# 4_Drivers.net
KiCad netlist of a schematic drawn in Altium Designer
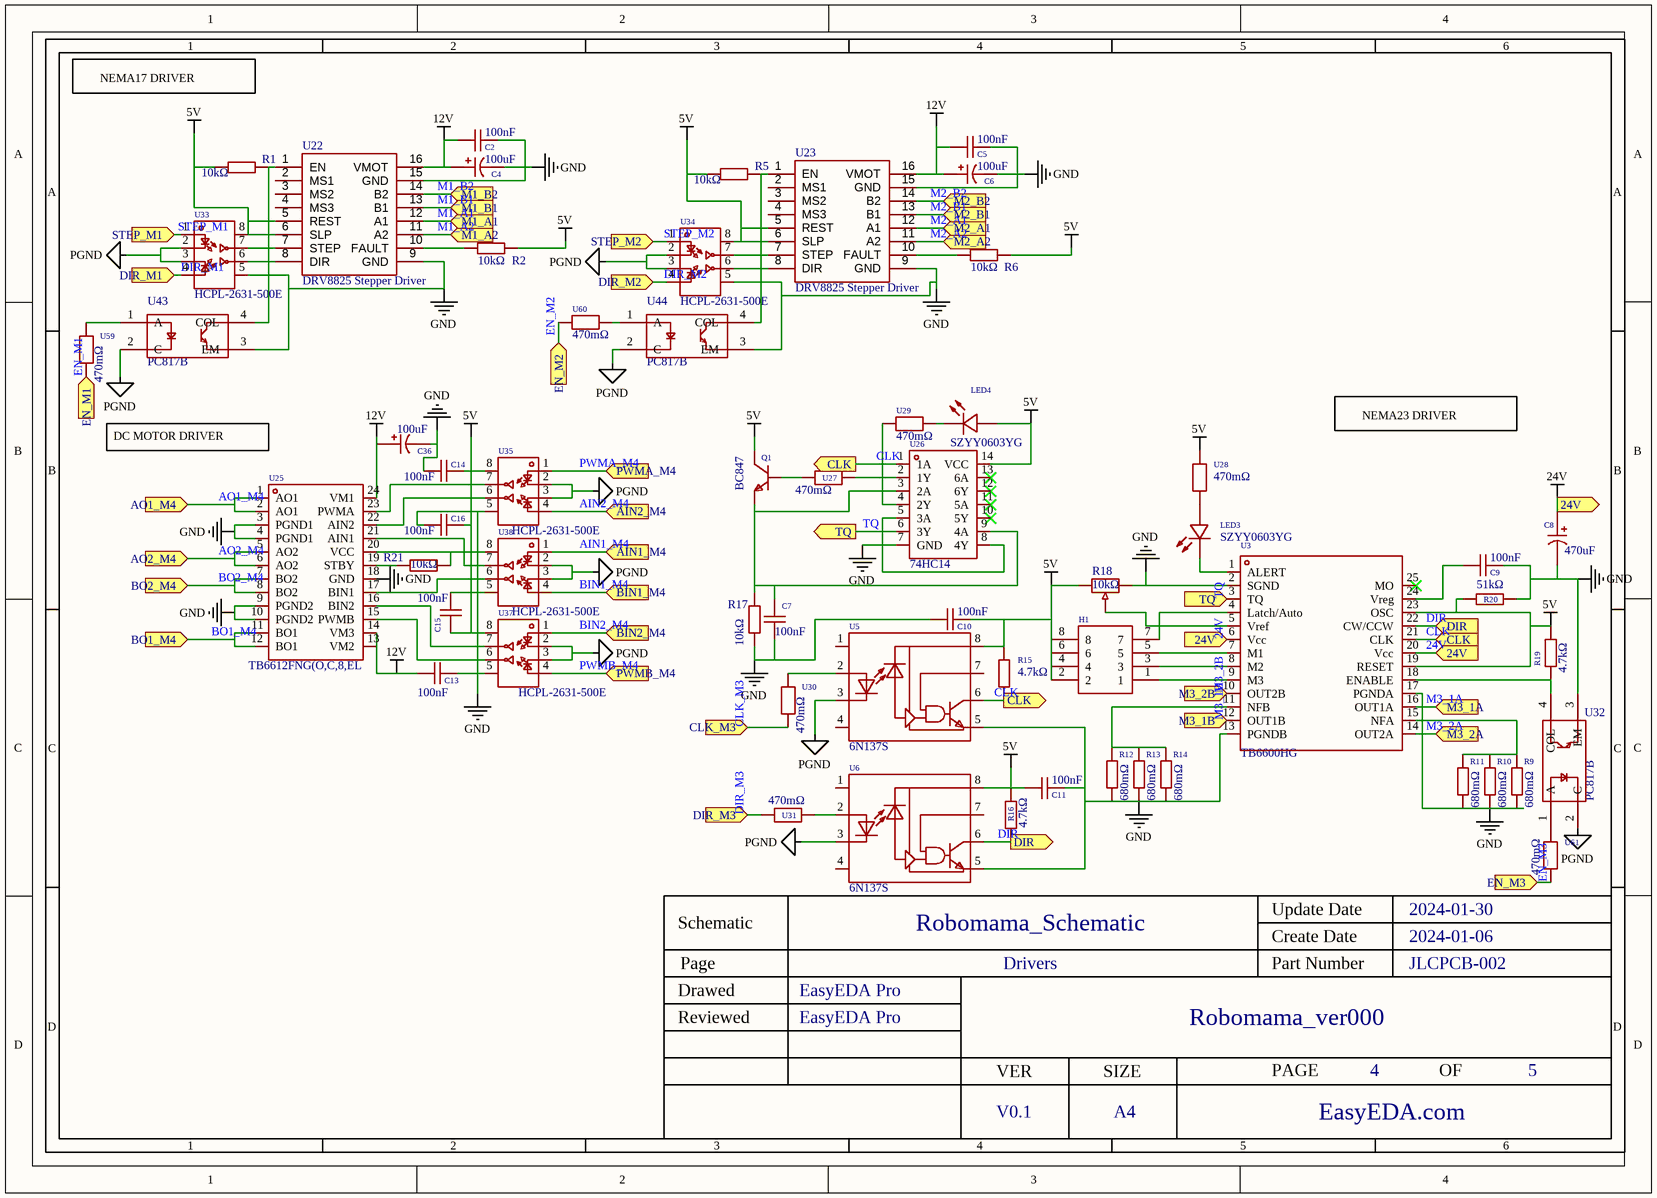
[diagram p0: 4_Drivers.schdoc]

(export (version "E")
  (design (tool "Eeschema 10.0.6"))
  (components
    (comp (ref "C2")
      (value "100nF")
      (footprint "C0603")
      (fields
        (field (name "MANUFACTURER") "FH(风华)")
        (field (name "MANUFACTURER PART") "0603B104K500NT")
        (field (name "TOLERANCE") "±10%")
      )
      (libsource (lib "altium-import") (part "root_0_0603B104K500NT_C30926_"))
    )
    (comp (ref "C4")
      (value "100uF")
      (footprint "CAP-SMD_BD6.3-L6.6-W6.6-LS7.2-FD")
      (fields
        (field (name "MANUFACTURER") "KNSCHA(科尼盛)")
        (field (name "MANUFACTURER PART") "RST100UF25V006")
        (field (name "TOLERANCE") "±20%")
      )
      (libsource (lib "altium-import") (part "root_0_RST100UF25V006_"))
    )
    (comp (ref "C5")
      (value "100nF")
      (footprint "C0603")
      (fields
        (field (name "MANUFACTURER") "FH(风华)")
        (field (name "MANUFACTURER PART") "0603B104K500NT")
        (field (name "TOLERANCE") "±10%")
      )
      (libsource (lib "altium-import") (part "root_0_0603B104K500NT_C30926_"))
    )
    (comp (ref "C6")
      (value "100uF")
      (footprint "CAP-SMD_BD6.3-L6.6-W6.6-LS7.2-FD")
      (fields
        (field (name "MANUFACTURER") "KNSCHA(科尼盛)")
        (field (name "MANUFACTURER PART") "RST100UF25V006")
        (field (name "TOLERANCE") "±20%")
      )
      (libsource (lib "altium-import") (part "root_0_RST100UF25V006_"))
    )
    (comp (ref "C7")
      (value "100nF")
      (footprint "C0603")
      (fields
        (field (name "MANUFACTURER") "FH(风华)")
        (field (name "MANUFACTURER PART") "0603B104K500NT")
        (field (name "TOLERANCE") "±10%")
      )
      (libsource (lib "altium-import") (part "root_1_0603B104K500NT_C30926_"))
    )
    (comp (ref "C8")
      (value "470uF")
      (footprint "CAP-SMD_BD12.5-L13.0-W13.0-LS14.0-FD")
      (fields
        (field (name "MANUFACTURER") "KNSCHA(科尼盛)")
        (field (name "MANUFACTURER PART") "RVT470UF50V34RV0133")
        (field (name "TOLERANCE") "±20%")
      )
      (libsource (lib "altium-import") (part "root_3_RVT470UF50V34RV0133_"))
    )
    (comp (ref "C9")
      (value "100nF")
      (footprint "C0603")
      (fields
        (field (name "MANUFACTURER") "FH(风华)")
        (field (name "MANUFACTURER PART") "0603B104K500NT")
        (field (name "TOLERANCE") "±10%")
      )
      (libsource (lib "altium-import") (part "root_0_0603B104K500NT_C30926_"))
    )
    (comp (ref "C10")
      (value "100nF")
      (footprint "C0603")
      (fields
        (field (name "MANUFACTURER") "FH(风华)")
        (field (name "MANUFACTURER PART") "0603B104K500NT")
        (field (name "TOLERANCE") "±10%")
      )
      (libsource (lib "altium-import") (part "root_0_0603B104K500NT_C30926_"))
    )
    (comp (ref "C11")
      (value "100nF")
      (footprint "C0603")
      (fields
        (field (name "MANUFACTURER") "FH(风华)")
        (field (name "MANUFACTURER PART") "0603B104K500NT")
        (field (name "TOLERANCE") "±10%")
      )
      (libsource (lib "altium-import") (part "root_0_0603B104K500NT_C30926_"))
    )
    (comp (ref "C13")
      (value "100nF")
      (footprint "C0603")
      (fields
        (field (name "MANUFACTURER") "FH(风华)")
        (field (name "MANUFACTURER PART") "0603B104K500NT")
        (field (name "TOLERANCE") "±10%")
      )
      (libsource (lib "altium-import") (part "root_0_0603B104K500NT_C30926_"))
    )
    (comp (ref "C14")
      (value "100nF")
      (footprint "C0603")
      (fields
        (field (name "MANUFACTURER") "FH(风华)")
        (field (name "MANUFACTURER PART") "0603B104K500NT")
        (field (name "TOLERANCE") "±10%")
      )
      (libsource (lib "altium-import") (part "root_0_0603B104K500NT_C30926_"))
    )
    (comp (ref "C15")
      (value "100nF")
      (footprint "C0603")
      (fields
        (field (name "MANUFACTURER") "FH(风华)")
        (field (name "MANUFACTURER PART") "0603B104K500NT")
        (field (name "TOLERANCE") "±10%")
      )
      (libsource (lib "altium-import") (part "root_3_0603B104K500NT_C30926_"))
    )
    (comp (ref "C16")
      (value "100nF")
      (footprint "C0603")
      (fields
        (field (name "MANUFACTURER") "FH(风华)")
        (field (name "MANUFACTURER PART") "0603B104K500NT")
        (field (name "TOLERANCE") "±10%")
      )
      (libsource (lib "altium-import") (part "root_0_0603B104K500NT_C30926_"))
    )
    (comp (ref "C36")
      (value "100uF")
      (footprint "CAP-SMD_BD6.3-L6.6-W6.6-LS7.2-FD")
      (fields
        (field (name "MANUFACTURER") "KNSCHA(科尼盛)")
        (field (name "MANUFACTURER PART") "RST100UF25V006")
        (field (name "TOLERANCE") "±20%")
      )
      (libsource (lib "altium-import") (part "root_0_RST100UF25V006_"))
    )
    (comp (ref "H1")
      (value "68602-108HLF")
      (footprint "HDR-TH_8P-P2.54-V-M-R2-C4-S2.54")
      (fields (field (name "MANUFACTURER") "Amphenol"))
      (libsource (lib "altium-import") (part "root_1_68602-108HLF_"))
    )
    (comp (ref "LED3")
      (value "SZYY0603YG")
      (footprint "LED0603-R-RD_GREEN")
      (description "Emitted Color:Green-yellow")
      (fields (field (name "MANUFACTURER") "yongyu(永裕光电)"))
      (libsource (lib "altium-import") (part "root_1_SZYY0603YG_"))
    )
    (comp (ref "LED4")
      (value "SZYY0603YG")
      (footprint "LED0603-R-RD_GREEN")
      (description "Emitted Color:Green-yellow")
      (fields (field (name "MANUFACTURER") "yongyu(永裕光电)"))
      (libsource (lib "altium-import") (part "root_0_SZYY0603YG_"))
    )
    (comp (ref "Q1")
      (value "BC847")
      (footprint "SOT-23-3_L2.9-W1.3-P1.90-LS2.4-BR")
      (fields (field (name "MANUFACTURER") "SHIKUES(时科)"))
      (libsource (lib "altium-import") (part "root_0_mirrored_BC847_C475630_"))
    )
    (comp (ref "R1")
      (value "10kΩ")
      (footprint "R0603")
      (fields
        (field (name "MANUFACTURER") "YAGEO(国巨)")
        (field (name "MANUFACTURER PART") "RC0603FR-0710KL")
        (field (name "TOLERANCE") "±1%")
      )
      (libsource (lib "altium-import") (part "root_2_RC0603FR-0710KL_"))
    )
    (comp (ref "R2")
      (value "10kΩ")
      (footprint "R0603")
      (fields
        (field (name "MANUFACTURER") "YAGEO(国巨)")
        (field (name "MANUFACTURER PART") "RC0603FR-0710KL")
        (field (name "TOLERANCE") "±1%")
      )
      (libsource (lib "altium-import") (part "root_2_RC0603FR-0710KL_"))
    )
    (comp (ref "R5")
      (value "10kΩ")
      (footprint "R0603")
      (fields
        (field (name "MANUFACTURER") "YAGEO(国巨)")
        (field (name "MANUFACTURER PART") "RC0603FR-0710KL")
        (field (name "TOLERANCE") "±1%")
      )
      (libsource (lib "altium-import") (part "root_2_RC0603FR-0710KL_"))
    )
    (comp (ref "R6")
      (value "10kΩ")
      (footprint "R0603")
      (fields
        (field (name "MANUFACTURER") "YAGEO(国巨)")
        (field (name "MANUFACTURER PART") "RC0603FR-0710KL")
        (field (name "TOLERANCE") "±1%")
      )
      (libsource (lib "altium-import") (part "root_2_RC0603FR-0710KL_"))
    )
    (comp (ref "R9")
      (value "680mΩ")
      (footprint "R1206")
      (fields
        (field (name "MANUFACTURER") "UNI-ROYAL(厚声)")
        (field (name "MANUFACTURER PART") "1206W4F680LT5E")
        (field (name "TOLERANCE") "±1%")
      )
      (libsource (lib "altium-import") (part "root_1_1206W4F680LT5E_"))
    )
    (comp (ref "R10")
      (value "680mΩ")
      (footprint "R1206")
      (fields
        (field (name "MANUFACTURER") "UNI-ROYAL(厚声)")
        (field (name "MANUFACTURER PART") "1206W4F680LT5E")
        (field (name "TOLERANCE") "±1%")
      )
      (libsource (lib "altium-import") (part "root_1_1206W4F680LT5E_"))
    )
    (comp (ref "R11")
      (value "680mΩ")
      (footprint "R1206")
      (fields
        (field (name "MANUFACTURER") "UNI-ROYAL(厚声)")
        (field (name "MANUFACTURER PART") "1206W4F680LT5E")
        (field (name "TOLERANCE") "±1%")
      )
      (libsource (lib "altium-import") (part "root_1_1206W4F680LT5E_"))
    )
    (comp (ref "R12")
      (value "680mΩ")
      (footprint "R1206")
      (fields
        (field (name "MANUFACTURER") "UNI-ROYAL(厚声)")
        (field (name "MANUFACTURER PART") "1206W4F680LT5E")
        (field (name "TOLERANCE") "±1%")
      )
      (libsource (lib "altium-import") (part "root_1_1206W4F680LT5E_"))
    )
    (comp (ref "R13")
      (value "680mΩ")
      (footprint "R1206")
      (fields
        (field (name "MANUFACTURER") "UNI-ROYAL(厚声)")
        (field (name "MANUFACTURER PART") "1206W4F680LT5E")
        (field (name "TOLERANCE") "±1%")
      )
      (libsource (lib "altium-import") (part "root_1_1206W4F680LT5E_"))
    )
    (comp (ref "R14")
      (value "680mΩ")
      (footprint "R1206")
      (fields
        (field (name "MANUFACTURER") "UNI-ROYAL(厚声)")
        (field (name "MANUFACTURER PART") "1206W4F680LT5E")
        (field (name "TOLERANCE") "±1%")
      )
      (libsource (lib "altium-import") (part "root_1_1206W4F680LT5E_"))
    )
    (comp (ref "R15")
      (value "4.7kΩ")
      (footprint "R0402")
      (fields
        (field (name "MANUFACTURER") "UNI-ROYAL(厚声)")
        (field (name "MANUFACTURER PART") "0402WGF4701TCE")
        (field (name "TOLERANCE") "±1%")
      )
      (libsource (lib "altium-import") (part "root_1_0402WGF4701TCE_"))
    )
    (comp (ref "R16")
      (value "4.7kΩ")
      (footprint "R0402")
      (fields
        (field (name "MANUFACTURER") "UNI-ROYAL(厚声)")
        (field (name "MANUFACTURER PART") "0402WGF4701TCE")
        (field (name "TOLERANCE") "±1%")
      )
      (libsource (lib "altium-import") (part "root_1_0402WGF4701TCE_"))
    )
    (comp (ref "R17")
      (value "10kΩ")
      (footprint "R0603")
      (fields
        (field (name "MANUFACTURER") "YAGEO(国巨)")
        (field (name "MANUFACTURER PART") "RC0603FR-0710KL")
        (field (name "TOLERANCE") "±1%")
      )
      (libsource (lib "altium-import") (part "root_3_RC0603FR-0710KL_"))
    )
    (comp (ref "R18")
      (value "10kΩ")
      (footprint "RES-ADJ-TH_3P-L9.6-W4.8-P2.50-R")
      (description "Resistance: Tolerance:±10% Tolerance:±10%")
      (fields
        (field (name "MANUFACTURER") "COPAL(科宝电子)")
        (field (name "MANUFACTURER PART") "CT-94EX 10K OHM (103)")
      )
      (libsource (lib "altium-import") (part "root_1_CT-94EX 10K OHM (103)_"))
    )
    (comp (ref "R19")
      (value "4.7kΩ")
      (footprint "R0402")
      (fields
        (field (name "MANUFACTURER") "UNI-ROYAL(厚声)")
        (field (name "MANUFACTURER PART") "0402WGF4701TCE")
        (field (name "TOLERANCE") "±1%")
      )
      (libsource (lib "altium-import") (part "root_1_0402WGF4701TCE_"))
    )
    (comp (ref "R20")
      (value "51kΩ")
      (footprint "R0603")
      (fields
        (field (name "MANUFACTURER") "UNI-ROYAL(厚声)")
        (field (name "MANUFACTURER PART") "0603WAF5102T5E")
        (field (name "TOLERANCE") "±1%")
      )
      (libsource (lib "altium-import") (part "root_2_0603WAF5102T5E_"))
    )
    (comp (ref "R21")
      (value "10kΩ")
      (footprint "R0603")
      (fields
        (field (name "MANUFACTURER") "YAGEO(国巨)")
        (field (name "MANUFACTURER PART") "RC0603FR-0710KL")
        (field (name "TOLERANCE") "±1%")
      )
      (libsource (lib "altium-import") (part "root_2_RC0603FR-0710KL_"))
    )
    (comp (ref "U3")
      (value "TB6600HG")
      (footprint "HZIP25-P-1.0_TB6600HG")
      (fields (field (name "MANUFACTURER") "TOSHIBA(东芝)"))
      (libsource (lib "altium-import") (part "root_0_TB6600HG_"))
    )
    (comp (ref "U5")
      (value "6N137S")
      (footprint "SOP-8_L9.8-W6.6-P2.54-LS10.3-BL")
      (fields (field (name "MANUFACTURER") "Slkor(萨科微)"))
      (libsource (lib "altium-import") (part "root_0_6N137S_"))
    )
    (comp (ref "U6")
      (value "6N137S")
      (footprint "SOP-8_L9.8-W6.6-P2.54-LS10.3-BL")
      (fields (field (name "MANUFACTURER") "Slkor(萨科微)"))
      (libsource (lib "altium-import") (part "root_0_6N137S_"))
    )
    (comp (ref "U22")
      (value "DRV8825 Stepper Driver")
      (footprint "DRV8825")
      (fields (field (name "MANUFACTURER") "Pololu") (field (name "MANUFACTURER PART") "DRV8825"))
      (libsource (lib "altium-import") (part "root_0_DRV8825 Stepper Driver_"))
    )
    (comp (ref "U23")
      (value "DRV8825 Stepper Driver")
      (footprint "DRV8825")
      (fields (field (name "MANUFACTURER") "Pololu") (field (name "MANUFACTURER PART") "DRV8825"))
      (libsource (lib "altium-import") (part "root_0_DRV8825 Stepper Driver_"))
    )
    (comp (ref "U25")
      (value "TB6612FNG(O,C,8,EL")
      (footprint "SSOP-24_L8.4-W5.8-P0.65-LS7.8-BL")
      (fields (field (name "MANUFACTURER") "TOSHIBA(东芝)"))
      (libsource (lib "altium-import") (part "root_0_TB6612FNG(O,C,8,EL_"))
    )
    (comp (ref "U26")
      (value "74HC14")
      (footprint "SOIC-14_L8.7-W3.9-P1.27-LS6.0-BL")
      (fields (field (name "MANUFACTURER") "JSMSEMI(杰盛微)"))
      (libsource (lib "altium-import") (part "root_0_74HC14_C5356103_"))
    )
    (comp (ref "U27")
      (value "470mΩ")
      (footprint "R0603")
      (fields
        (field (name "MANUFACTURER") "FOJAN(富捷)")
        (field (name "MANUFACTURER PART") "FRL0603FR470TS")
        (field (name "TOLERANCE") "±1%")
      )
      (libsource (lib "altium-import") (part "root_0_FRL0603FR470TS_"))
    )
    (comp (ref "U28")
      (value "470mΩ")
      (footprint "R0603")
      (fields
        (field (name "MANUFACTURER") "FOJAN(富捷)")
        (field (name "MANUFACTURER PART") "FRL0603FR470TS")
        (field (name "TOLERANCE") "±1%")
      )
      (libsource (lib "altium-import") (part "root_1_FRL0603FR470TS_"))
    )
    (comp (ref "U29")
      (value "470mΩ")
      (footprint "R0603")
      (fields
        (field (name "MANUFACTURER") "FOJAN(富捷)")
        (field (name "MANUFACTURER PART") "FRL0603FR470TS")
        (field (name "TOLERANCE") "±1%")
      )
      (libsource (lib "altium-import") (part "root_0_FRL0603FR470TS_"))
    )
    (comp (ref "U30")
      (value "470mΩ")
      (footprint "R0603")
      (fields
        (field (name "MANUFACTURER") "FOJAN(富捷)")
        (field (name "MANUFACTURER PART") "FRL0603FR470TS")
        (field (name "TOLERANCE") "±1%")
      )
      (libsource (lib "altium-import") (part "root_3_FRL0603FR470TS_"))
    )
    (comp (ref "U31")
      (value "470mΩ")
      (footprint "R0603")
      (fields
        (field (name "MANUFACTURER") "FOJAN(富捷)")
        (field (name "MANUFACTURER PART") "FRL0603FR470TS")
        (field (name "TOLERANCE") "±1%")
      )
      (libsource (lib "altium-import") (part "root_2_FRL0603FR470TS_"))
    )
    (comp (ref "U32")
      (value "PC817B")
      (footprint "OPTO-SMD-4_L4.6-W6.5-P2.54-LS10.3-TL")
      (fields (field (name "MANUFACTURER") "GOODWORK(固得沃克)"))
      (libsource (lib "altium-import") (part "root_1_PC817B_C3025163_"))
    )
    (comp (ref "U33")
      (value "HCPL-2631-500E")
      (footprint "OPTO-SMD-8P_L9.7-W6.4-P2.54-LS9.7-BL")
      (fields (field (name "MANUFACTURER") "Broadcom/AVAGO(安华高)"))
      (libsource (lib "altium-import") (part "root_0_HCPL-2631-500E_"))
    )
    (comp (ref "U34")
      (value "HCPL-2631-500E")
      (footprint "OPTO-SMD-8P_L9.7-W6.4-P2.54-LS9.7-BL")
      (fields (field (name "MANUFACTURER") "Broadcom/AVAGO(安华高)"))
      (libsource (lib "altium-import") (part "root_0_HCPL-2631-500E_"))
    )
    (comp (ref "U35")
      (value "HCPL-2631-500E")
      (footprint "OPTO-SMD-8P_L9.7-W6.4-P2.54-LS9.7-BL")
      (fields (field (name "MANUFACTURER") "Broadcom/AVAGO(安华高)"))
      (libsource (lib "altium-import") (part "root_0_mirrored_HCPL-2631-500E_"))
    )
    (comp (ref "U37")
      (value "HCPL-2631-500E")
      (footprint "OPTO-SMD-8P_L9.7-W6.4-P2.54-LS9.7-BL")
      (fields (field (name "MANUFACTURER") "Broadcom/AVAGO(安华高)"))
      (libsource (lib "altium-import") (part "root_0_mirrored_HCPL-2631-500E_"))
    )
    (comp (ref "U38")
      (value "HCPL-2631-500E")
      (footprint "OPTO-SMD-8P_L9.7-W6.4-P2.54-LS9.7-BL")
      (fields (field (name "MANUFACTURER") "Broadcom/AVAGO(安华高)"))
      (libsource (lib "altium-import") (part "root_0_mirrored_HCPL-2631-500E_"))
    )
    (comp (ref "U43")
      (value "PC817B")
      (footprint "OPTO-SMD-4_L4.6-W6.5-P2.54-LS10.3-TL")
      (fields (field (name "MANUFACTURER") "GOODWORK(固得沃克)"))
      (libsource (lib "altium-import") (part "root_0_PC817B_C3025163_"))
    )
    (comp (ref "U44")
      (value "PC817B")
      (footprint "OPTO-SMD-4_L4.6-W6.5-P2.54-LS10.3-TL")
      (fields (field (name "MANUFACTURER") "GOODWORK(固得沃克)"))
      (libsource (lib "altium-import") (part "root_0_PC817B_C3025163_"))
    )
    (comp (ref "U59")
      (value "470mΩ")
      (footprint "R0603")
      (fields
        (field (name "MANUFACTURER") "FOJAN(富捷)")
        (field (name "MANUFACTURER PART") "FRL0603FR470TS")
        (field (name "TOLERANCE") "±1%")
      )
      (libsource (lib "altium-import") (part "root_3_FRL0603FR470TS_"))
    )
    (comp (ref "U60")
      (value "470mΩ")
      (footprint "R0603")
      (fields
        (field (name "MANUFACTURER") "FOJAN(富捷)")
        (field (name "MANUFACTURER PART") "FRL0603FR470TS")
        (field (name "TOLERANCE") "±1%")
      )
      (libsource (lib "altium-import") (part "root_0_FRL0603FR470TS_"))
    )
    (comp (ref "U61")
      (value "470mΩ")
      (footprint "R0603")
      (fields
        (field (name "MANUFACTURER") "FOJAN(富捷)")
        (field (name "MANUFACTURER PART") "FRL0603FR470TS")
        (field (name "TOLERANCE") "±1%")
      )
      (libsource (lib "altium-import") (part "root_3_FRL0603FR470TS_"))
    )
  )
  (nets
    (net (code "1") (name "/AIN1_M4") (class "Default")
      (node (ref "U38") (pin "1") (pinfunction "ANODE_1_1") (pintype "passive"))
    )
    (net (code "2") (name "/AIN2_M4") (class "Default")
      (node (ref "U35") (pin "4") (pinfunction "ANODE_2_4") (pintype "passive"))
    )
    (net (code "3") (name "/AO1_M4") (class "Default")
      (node (ref "U25") (pin "1") (pinfunction "AO1_1") (pintype "passive"))
      (node (ref "U25") (pin "2") (pinfunction "AO1_2") (pintype "passive"))
    )
    (net (code "4") (name "/AO2_M4") (class "Default")
      (node (ref "U25") (pin "5") (pinfunction "AO2_5") (pintype "passive"))
      (node (ref "U25") (pin "6") (pinfunction "AO2_6") (pintype "passive"))
    )
    (net (code "5") (name "/BIN1_M4") (class "Default")
      (node (ref "U38") (pin "4") (pinfunction "ANODE_2_4") (pintype "passive"))
    )
    (net (code "6") (name "/BIN2_M4") (class "Default")
      (node (ref "U37") (pin "1") (pinfunction "ANODE_1_1") (pintype "passive"))
    )
    (net (code "7") (name "/BO1_M4") (class "Default")
      (node (ref "U25") (pin "11") (pinfunction "BO1_11") (pintype "passive"))
      (node (ref "U25") (pin "12") (pinfunction "BO1_12") (pintype "passive"))
    )
    (net (code "8") (name "/BO2_M4") (class "Default")
      (node (ref "U25") (pin "7") (pinfunction "BO2_7") (pintype "passive"))
      (node (ref "U25") (pin "8") (pinfunction "BO2_8") (pintype "passive"))
    )
    (net (code "9") (name "/CLK") (class "Default")
      (node (ref "R15") (pin "1") (pinfunction "1_1") (pintype "passive"))
      (node (ref "U26") (pin "1") (pinfunction "1A_1") (pintype "passive"))
      (node (ref "U3") (pin "21") (pinfunction "CLK_21") (pintype "passive"))
      (node (ref "U5") (pin "6") (pinfunction "6_6") (pintype "passive"))
    )
    (net (code "10") (name "/CLK_M3") (class "Default")
      (node (ref "U30") (pin "2") (pinfunction "2_2") (pintype "passive"))
    )
    (net (code "11") (name "/DIR") (class "Default")
      (node (ref "R16") (pin "1") (pinfunction "1_1") (pintype "passive"))
      (node (ref "U3") (pin "22") (pinfunction "CW/CCW_22") (pintype "passive"))
      (node (ref "U6") (pin "6") (pinfunction "6_6") (pintype "passive"))
    )
    (net (code "12") (name "/DIR_M1") (class "Default")
      (node (ref "U33") (pin "4") (pinfunction "ANODE_2_4") (pintype "passive"))
    )
    (net (code "13") (name "/DIR_M2") (class "Default")
      (node (ref "U34") (pin "4") (pinfunction "ANODE_2_4") (pintype "passive"))
    )
    (net (code "14") (name "/DIR_M3") (class "Default")
      (node (ref "U31") (pin "2") (pinfunction "2_2") (pintype "passive"))
    )
    (net (code "15") (name "/EN_M1") (class "Default")
      (node (ref "U59") (pin "2") (pinfunction "2_2") (pintype "passive"))
    )
    (net (code "16") (name "/EN_M2") (class "Default")
      (node (ref "U60") (pin "1") (pinfunction "1_1") (pintype "passive"))
    )
    (net (code "17") (name "/EN_M3") (class "Default")
      (node (ref "U61") (pin "2") (pinfunction "2_2") (pintype "passive"))
    )
    (net (code "18") (name "/M1_A1") (class "Default")
      (node (ref "U22") (pin "12") (pinfunction "A1_12") (pintype "passive"))
    )
    (net (code "19") (name "/M1_A2") (class "Default")
      (node (ref "U22") (pin "11") (pinfunction "A2_11") (pintype "passive"))
    )
    (net (code "20") (name "/M1_B1") (class "Default")
      (node (ref "U22") (pin "13") (pinfunction "B1_13") (pintype "passive"))
    )
    (net (code "21") (name "/M1_B2") (class "Default")
      (node (ref "U22") (pin "14") (pinfunction "B2_14") (pintype "passive"))
    )
    (net (code "22") (name "/M2_A1") (class "Default")
      (node (ref "U23") (pin "12") (pinfunction "A1_12") (pintype "passive"))
    )
    (net (code "23") (name "/M2_A2") (class "Default")
      (node (ref "U23") (pin "11") (pinfunction "A2_11") (pintype "passive"))
    )
    (net (code "24") (name "/M2_B1") (class "Default")
      (node (ref "U23") (pin "13") (pinfunction "B1_13") (pintype "passive"))
    )
    (net (code "25") (name "/M2_B2") (class "Default")
      (node (ref "U23") (pin "14") (pinfunction "B2_14") (pintype "passive"))
    )
    (net (code "26") (name "/M3_1A") (class "Default")
      (node (ref "U3") (pin "16") (pinfunction "OUT1A_16") (pintype "passive"))
    )
    (net (code "27") (name "/M3_1B") (class "Default")
      (node (ref "U3") (pin "12") (pinfunction "OUT1B_12") (pintype "passive"))
    )
    (net (code "28") (name "/M3_2A") (class "Default")
      (node (ref "U3") (pin "14") (pinfunction "OUT2A_14") (pintype "passive"))
    )
    (net (code "29") (name "/M3_2B") (class "Default")
      (node (ref "U3") (pin "10") (pinfunction "OUT2B_10") (pintype "passive"))
    )
    (net (code "30") (name "/PWMA_M4") (class "Default")
      (node (ref "U35") (pin "1") (pinfunction "ANODE_1_1") (pintype "passive"))
    )
    (net (code "31") (name "/PWMB_M4") (class "Default")
      (node (ref "U37") (pin "4") (pinfunction "ANODE_2_4") (pintype "passive"))
    )
    (net (code "32") (name "/STEP_M1") (class "Default")
      (node (ref "U33") (pin "1") (pinfunction "ANODE_1_1") (pintype "passive"))
    )
    (net (code "33") (name "/STEP_M2") (class "Default")
      (node (ref "U34") (pin "1") (pinfunction "ANODE_1_1") (pintype "passive"))
    )
    (net (code "34") (name "/TQ") (class "Default")
      (node (ref "U26") (pin "6") (pinfunction "3Y_6") (pintype "passive"))
      (node (ref "U3") (pin "3") (pinfunction "TQ_3") (pintype "passive"))
    )
    (net (code "35") (name "5V") (class "Default")
      (node (ref "C10") (pin "2") (pinfunction "2_2") (pintype "passive"))
      (node (ref "C11") (pin "1") (pinfunction "1_1") (pintype "passive"))
      (node (ref "C14") (pin "2") (pinfunction "2_2") (pintype "passive"))
      (node (ref "C15") (pin "2") (pinfunction "2_2") (pintype "passive"))
      (node (ref "C16") (pin "2") (pinfunction "2_2") (pintype "passive"))
      (node (ref "H1") (pin "2") (pinfunction "2_2") (pintype "passive"))
      (node (ref "H1") (pin "4") (pinfunction "4_4") (pintype "passive"))
      (node (ref "H1") (pin "6") (pinfunction "6_6") (pintype "passive"))
      (node (ref "H1") (pin "8") (pinfunction "8_8") (pintype "passive"))
      (node (ref "LED4") (pin "1") (pinfunction "+_1") (pintype "passive"))
      (node (ref "Q1") (pin "3") (pinfunction "C_3") (pintype "passive"))
      (node (ref "R1") (pin "2") (pinfunction "2_2") (pintype "passive"))
      (node (ref "R15") (pin "2") (pinfunction "2_2") (pintype "passive"))
      (node (ref "R16") (pin "2") (pinfunction "2_2") (pintype "passive"))
      (node (ref "R18") (pin "3") (pinfunction "3_3") (pintype "passive"))
      (node (ref "R19") (pin "2") (pinfunction "2_2") (pintype "passive"))
      (node (ref "R2") (pin "1") (pinfunction "1_1") (pintype "passive"))
      (node (ref "R20") (pin "2") (pinfunction "2_2") (pintype "passive"))
      (node (ref "R21") (pin "1") (pinfunction "1_1") (pintype "passive"))
      (node (ref "R5") (pin "2") (pinfunction "2_2") (pintype "passive"))
      (node (ref "R6") (pin "1") (pinfunction "1_1") (pintype "passive"))
      (node (ref "U22") (pin "5") (pinfunction "REST_5") (pintype "passive"))
      (node (ref "U22") (pin "6") (pinfunction "SLP_6") (pintype "passive"))
      (node (ref "U23") (pin "5") (pinfunction "REST_5") (pintype "passive"))
      (node (ref "U23") (pin "6") (pinfunction "SLP_6") (pintype "passive"))
      (node (ref "U25") (pin "20") (pinfunction "VCC_20") (pintype "passive"))
      (node (ref "U26") (pin "14") (pinfunction "VCC_14") (pintype "passive"))
      (node (ref "U28") (pin "2") (pinfunction "2_2") (pintype "passive"))
      (node (ref "U3") (pin "19") (pinfunction "RESET_19") (pintype "passive"))
      (node (ref "U3") (pin "23") (pinfunction "OSC_23") (pintype "passive"))
      (node (ref "U33") (pin "8") (pinfunction "VCC_8") (pintype "passive"))
      (node (ref "U34") (pin "8") (pinfunction "VCC_8") (pintype "passive"))
      (node (ref "U35") (pin "8") (pinfunction "VCC_8") (pintype "passive"))
      (node (ref "U37") (pin "8") (pinfunction "VCC_8") (pintype "passive"))
      (node (ref "U38") (pin "8") (pinfunction "VCC_8") (pintype "passive"))
      (node (ref "U5") (pin "8") (pinfunction "8_8") (pintype "passive"))
      (node (ref "U6") (pin "8") (pinfunction "8_8") (pintype "passive"))
    )
    (net (code "36") (name "12V") (class "Default")
      (node (ref "C13") (pin "1") (pinfunction "1_1") (pintype "passive"))
      (node (ref "C2") (pin "1") (pinfunction "1_1") (pintype "passive"))
      (node (ref "C36") (pin "1") (pinfunction "1_1") (pintype "passive"))
      (node (ref "C4") (pin "1") (pinfunction "1_1") (pintype "passive"))
      (node (ref "C5") (pin "1") (pinfunction "1_1") (pintype "passive"))
      (node (ref "C6") (pin "1") (pinfunction "1_1") (pintype "passive"))
      (node (ref "U22") (pin "16") (pinfunction "VMOT_16") (pintype "passive"))
      (node (ref "U23") (pin "16") (pinfunction "VMOT_16") (pintype "passive"))
      (node (ref "U25") (pin "13") (pinfunction "VM2_13") (pintype "passive"))
      (node (ref "U25") (pin "14") (pinfunction "VM3_14") (pintype "passive"))
      (node (ref "U25") (pin "24") (pinfunction "VM1_24") (pintype "passive"))
    )
    (net (code "37") (name "24V") (class "Default")
      (node (ref "C8") (pin "1") (pinfunction "1_1") (pintype "passive"))
      (node (ref "U3") (pin "20") (pinfunction "Vcc_20") (pintype "passive"))
      (node (ref "U3") (pin "6") (pinfunction "Vcc_6") (pintype "passive"))
    )
    (net (code "38") (name "GND") (class "Default")
      (node (ref "C10") (pin "1") (pinfunction "1_1") (pintype "passive"))
      (node (ref "C11") (pin "2") (pinfunction "2_2") (pintype "passive"))
      (node (ref "C13") (pin "2") (pinfunction "2_2") (pintype "passive"))
      (node (ref "C14") (pin "1") (pinfunction "1_1") (pintype "passive"))
      (node (ref "C15") (pin "1") (pinfunction "1_1") (pintype "passive"))
      (node (ref "C16") (pin "1") (pinfunction "1_1") (pintype "passive"))
      (node (ref "C2") (pin "2") (pinfunction "2_2") (pintype "passive"))
      (node (ref "C36") (pin "2") (pinfunction "2_2") (pintype "passive"))
      (node (ref "C4") (pin "2") (pinfunction "2_2") (pintype "passive"))
      (node (ref "C5") (pin "2") (pinfunction "2_2") (pintype "passive"))
      (node (ref "C6") (pin "2") (pinfunction "2_2") (pintype "passive"))
      (node (ref "C7") (pin "1") (pinfunction "1_1") (pintype "passive"))
      (node (ref "C8") (pin "2") (pinfunction "2_2") (pintype "passive"))
      (node (ref "C9") (pin "2") (pinfunction "2_2") (pintype "passive"))
      (node (ref "R10") (pin "1") (pinfunction "1_1") (pintype "passive"))
      (node (ref "R11") (pin "1") (pinfunction "1_1") (pintype "passive"))
      (node (ref "R12") (pin "1") (pinfunction "1_1") (pintype "passive"))
      (node (ref "R13") (pin "1") (pinfunction "1_1") (pintype "passive"))
      (node (ref "R14") (pin "1") (pinfunction "1_1") (pintype "passive"))
      (node (ref "R17") (pin "2") (pinfunction "2_2") (pintype "passive"))
      (node (ref "R18") (pin "1") (pinfunction "1_1") (pintype "passive"))
      (node (ref "R20") (pin "1") (pinfunction "1_1") (pintype "passive"))
      (node (ref "R9") (pin "1") (pinfunction "1_1") (pintype "passive"))
      (node (ref "U22") (pin "15") (pinfunction "GND_15") (pintype "passive"))
      (node (ref "U22") (pin "9") (pinfunction "GND_9") (pintype "passive"))
      (node (ref "U23") (pin "15") (pinfunction "GND_15") (pintype "passive"))
      (node (ref "U23") (pin "9") (pinfunction "GND_9") (pintype "passive"))
      (node (ref "U25") (pin "10") (pinfunction "PGND2_10") (pintype "passive"))
      (node (ref "U25") (pin "18") (pinfunction "GND_18") (pintype "passive"))
      (node (ref "U25") (pin "3") (pinfunction "PGND1_3") (pintype "passive"))
      (node (ref "U25") (pin "4") (pinfunction "PGND1_4") (pintype "passive"))
      (node (ref "U25") (pin "9") (pinfunction "PGND2_9") (pintype "passive"))
      (node (ref "U26") (pin "7") (pinfunction "GND_7") (pintype "passive"))
      (node (ref "U3") (pin "13") (pinfunction "PGNDB_13") (pintype "passive"))
      (node (ref "U3") (pin "17") (pinfunction "PGNDA_17") (pintype "passive"))
      (node (ref "U3") (pin "2") (pinfunction "SGND_2") (pintype "passive"))
      (node (ref "U32") (pin "3") (pinfunction "EM_3") (pintype "passive"))
      (node (ref "U33") (pin "5") (pinfunction "GND_5") (pintype "passive"))
      (node (ref "U34") (pin "5") (pinfunction "GND_5") (pintype "passive"))
      (node (ref "U35") (pin "5") (pinfunction "GND_5") (pintype "passive"))
      (node (ref "U37") (pin "5") (pinfunction "GND_5") (pintype "passive"))
      (node (ref "U38") (pin "5") (pinfunction "GND_5") (pintype "passive"))
      (node (ref "U43") (pin "3") (pinfunction "EM_3") (pintype "passive"))
      (node (ref "U44") (pin "3") (pinfunction "EM_3") (pintype "passive"))
      (node (ref "U5") (pin "5") (pinfunction "5_5") (pintype "passive"))
      (node (ref "U6") (pin "5") (pinfunction "5_5") (pintype "passive"))
    )
    (net (code "39") (name "Net-(LED3-+)") (class "Default")
      (node (ref "LED3") (pin "1") (pinfunction "+_1") (pintype "passive"))
      (node (ref "U28") (pin "1") (pinfunction "1_1") (pintype "passive"))
    )
    (net (code "40") (name "Net-(LED3--)") (class "Default")
      (node (ref "LED3") (pin "2") (pinfunction "-_2") (pintype "passive"))
      (node (ref "U3") (pin "1") (pinfunction "ALERT_1") (pintype "passive"))
    )
    (net (code "41") (name "Net-(LED4--)") (class "Default")
      (node (ref "LED4") (pin "2") (pinfunction "-_2") (pintype "passive"))
      (node (ref "U29") (pin "2") (pinfunction "2_2") (pintype "passive"))
    )
    (net (code "42") (name "Net-(Q1-B)") (class "Default")
      (node (ref "Q1") (pin "1") (pinfunction "B_1") (pintype "passive"))
      (node (ref "U27") (pin "1") (pinfunction "1_1") (pintype "passive"))
    )
    (net (code "43") (name "Net-(Q1-E)") (class "Default")
      (node (ref "C7") (pin "2") (pinfunction "2_2") (pintype "passive"))
      (node (ref "Q1") (pin "2") (pinfunction "E_2") (pintype "passive"))
      (node (ref "R17") (pin "1") (pinfunction "1_1") (pintype "passive"))
      (node (ref "U26") (pin "3") (pinfunction "2A_3") (pintype "passive"))
      (node (ref "U26") (pin "9") (pinfunction "4A_9") (pintype "passive"))
    )
    (net (code "44") (name "Net-(U3-ENABLE)") (class "Default")
      (node (ref "R19") (pin "1") (pinfunction "1_1") (pintype "passive"))
      (node (ref "U3") (pin "18") (pinfunction "ENABLE_18") (pintype "passive"))
      (node (ref "U32") (pin "4") (pinfunction "COL_4") (pintype "passive"))
    )
    (net (code "45") (name "Net-(U3-Latch{slash}Auto)") (class "Default")
      (node (ref "H1") (pin "7") (pinfunction "7_7") (pintype "passive"))
      (node (ref "U3") (pin "4") (pinfunction "Latch/Auto_4") (pintype "passive"))
    )
    (net (code "46") (name "Net-(U3-M1)") (class "Default")
      (node (ref "H1") (pin "5") (pinfunction "5_5") (pintype "passive"))
      (node (ref "U3") (pin "7") (pinfunction "M1_7") (pintype "passive"))
    )
    (net (code "47") (name "Net-(U3-M2)") (class "Default")
      (node (ref "H1") (pin "3") (pinfunction "3_3") (pintype "passive"))
      (node (ref "U3") (pin "8") (pinfunction "M2_8") (pintype "passive"))
    )
    (net (code "48") (name "Net-(U3-M3)") (class "Default")
      (node (ref "H1") (pin "1") (pinfunction "1_1") (pintype "passive"))
      (node (ref "U3") (pin "9") (pinfunction "M3_9") (pintype "passive"))
    )
    (net (code "49") (name "Net-(U3-NFA)") (class "Default")
      (node (ref "R10") (pin "2") (pinfunction "2_2") (pintype "passive"))
      (node (ref "R11") (pin "2") (pinfunction "2_2") (pintype "passive"))
      (node (ref "R9") (pin "2") (pinfunction "2_2") (pintype "passive"))
      (node (ref "U3") (pin "15") (pinfunction "NFA_15") (pintype "passive"))
    )
    (net (code "50") (name "Net-(U3-NFB)") (class "Default")
      (node (ref "R12") (pin "2") (pinfunction "2_2") (pintype "passive"))
      (node (ref "R13") (pin "2") (pinfunction "2_2") (pintype "passive"))
      (node (ref "R14") (pin "2") (pinfunction "2_2") (pintype "passive"))
      (node (ref "U3") (pin "11") (pinfunction "NFB_11") (pintype "passive"))
    )
    (net (code "51") (name "Net-(U3-Vref)") (class "Default")
      (node (ref "R18") (pin "2") (pinfunction "2_2") (pintype "passive"))
      (node (ref "U3") (pin "5") (pinfunction "Vref_5") (pintype "passive"))
    )
    (net (code "52") (name "Net-(U3-Vreg)") (class "Default")
      (node (ref "C9") (pin "1") (pinfunction "1_1") (pintype "passive"))
      (node (ref "U3") (pin "24") (pinfunction "Vreg_24") (pintype "passive"))
    )
    (net (code "53") (name "Net-(U22-DIR)") (class "Default")
      (node (ref "U22") (pin "8") (pinfunction "DIR_8") (pintype "passive"))
      (node (ref "U33") (pin "6") (pinfunction "VO2_6") (pintype "passive"))
    )
    (net (code "54") (name "Net-(U22-EN)") (class "Default")
      (node (ref "R1") (pin "1") (pinfunction "1_1") (pintype "passive"))
      (node (ref "U22") (pin "1") (pinfunction "EN_1") (pintype "passive"))
      (node (ref "U43") (pin "4") (pinfunction "COL_4") (pintype "passive"))
    )
    (net (code "55") (name "Net-(U22-FAULT)") (class "Default")
      (node (ref "R2") (pin "2") (pinfunction "2_2") (pintype "passive"))
      (node (ref "U22") (pin "10") (pinfunction "FAULT_10") (pintype "passive"))
    )
    (net (code "56") (name "Net-(U22-STEP)") (class "Default")
      (node (ref "U22") (pin "7") (pinfunction "STEP_7") (pintype "passive"))
      (node (ref "U33") (pin "7") (pinfunction "VO1_7") (pintype "passive"))
    )
    (net (code "57") (name "Net-(U23-DIR)") (class "Default")
      (node (ref "U23") (pin "8") (pinfunction "DIR_8") (pintype "passive"))
      (node (ref "U34") (pin "6") (pinfunction "VO2_6") (pintype "passive"))
    )
    (net (code "58") (name "Net-(U23-EN)") (class "Default")
      (node (ref "R5") (pin "1") (pinfunction "1_1") (pintype "passive"))
      (node (ref "U23") (pin "1") (pinfunction "EN_1") (pintype "passive"))
      (node (ref "U44") (pin "4") (pinfunction "COL_4") (pintype "passive"))
    )
    (net (code "59") (name "Net-(U23-FAULT)") (class "Default")
      (node (ref "R6") (pin "2") (pinfunction "2_2") (pintype "passive"))
      (node (ref "U23") (pin "10") (pinfunction "FAULT_10") (pintype "passive"))
    )
    (net (code "60") (name "Net-(U23-STEP)") (class "Default")
      (node (ref "U23") (pin "7") (pinfunction "STEP_7") (pintype "passive"))
      (node (ref "U34") (pin "7") (pinfunction "VO1_7") (pintype "passive"))
    )
    (net (code "61") (name "Net-(U25-AIN1)") (class "Default")
      (node (ref "U25") (pin "21") (pinfunction "AIN1_21") (pintype "passive"))
      (node (ref "U38") (pin "7") (pinfunction "VO1_7") (pintype "passive"))
    )
    (net (code "62") (name "Net-(U25-AIN2)") (class "Default")
      (node (ref "U25") (pin "22") (pinfunction "AIN2_22") (pintype "passive"))
      (node (ref "U35") (pin "6") (pinfunction "VO2_6") (pintype "passive"))
    )
    (net (code "63") (name "Net-(U25-BIN1)") (class "Default")
      (node (ref "U25") (pin "17") (pinfunction "BIN1_17") (pintype "passive"))
      (node (ref "U38") (pin "6") (pinfunction "VO2_6") (pintype "passive"))
    )
    (net (code "64") (name "Net-(U25-BIN2)") (class "Default")
      (node (ref "U25") (pin "16") (pinfunction "BIN2_16") (pintype "passive"))
      (node (ref "U37") (pin "7") (pinfunction "VO1_7") (pintype "passive"))
    )
    (net (code "65") (name "Net-(U25-PWMA)") (class "Default")
      (node (ref "U25") (pin "23") (pinfunction "PWMA_23") (pintype "passive"))
      (node (ref "U35") (pin "7") (pinfunction "VO1_7") (pintype "passive"))
    )
    (net (code "66") (name "Net-(U25-PWMB)") (class "Default")
      (node (ref "U25") (pin "15") (pinfunction "PWMB_15") (pintype "passive"))
      (node (ref "U37") (pin "6") (pinfunction "VO2_6") (pintype "passive"))
    )
    (net (code "67") (name "Net-(U25-STBY)") (class "Default")
      (node (ref "R21") (pin "2") (pinfunction "2_2") (pintype "passive"))
      (node (ref "U25") (pin "19") (pinfunction "STBY_19") (pintype "passive"))
    )
    (net (code "68") (name "Net-(U26-1Y)") (class "Default")
      (node (ref "U26") (pin "2") (pinfunction "1Y_2") (pintype "passive"))
      (node (ref "U27") (pin "2") (pinfunction "2_2") (pintype "passive"))
    )
    (net (code "69") (name "Net-(U26-2Y)") (class "Default")
      (node (ref "U26") (pin "4") (pinfunction "2Y_4") (pintype "passive"))
      (node (ref "U29") (pin "1") (pinfunction "1_1") (pintype "passive"))
    )
    (net (code "70") (name "Net-(U26-3A)") (class "Default")
      (node (ref "U26") (pin "5") (pinfunction "3A_5") (pintype "passive"))
      (node (ref "U26") (pin "8") (pinfunction "4Y_8") (pintype "passive"))
    )
    (net (code "71") (name "Net-(U30-Pad1)") (class "Default")
      (node (ref "U30") (pin "1") (pinfunction "1_1") (pintype "passive"))
      (node (ref "U5") (pin "2") (pinfunction "2_2") (pintype "passive"))
    )
    (net (code "72") (name "Net-(U31-Pad1)") (class "Default")
      (node (ref "U31") (pin "1") (pinfunction "1_1") (pintype "passive"))
      (node (ref "U6") (pin "2") (pinfunction "2_2") (pintype "passive"))
    )
    (net (code "73") (name "Net-(U32-A)") (class "Default")
      (node (ref "U32") (pin "1") (pinfunction "A_1") (pintype "passive"))
      (node (ref "U61") (pin "1") (pinfunction "1_1") (pintype "passive"))
    )
    (net (code "74") (name "Net-(U43-A)") (class "Default")
      (node (ref "U43") (pin "1") (pinfunction "A_1") (pintype "passive"))
      (node (ref "U59") (pin "1") (pinfunction "1_1") (pintype "passive"))
    )
    (net (code "75") (name "Net-(U44-A)") (class "Default")
      (node (ref "U44") (pin "1") (pinfunction "A_1") (pintype "passive"))
      (node (ref "U60") (pin "2") (pinfunction "2_2") (pintype "passive"))
    )
    (net (code "76") (name "PGND") (class "Default")
      (node (ref "U32") (pin "2") (pinfunction "C_2") (pintype "passive"))
      (node (ref "U33") (pin "2") (pinfunction "CATHODE_1_2") (pintype "passive"))
      (node (ref "U33") (pin "3") (pinfunction "CATHODE_2_3") (pintype "passive"))
      (node (ref "U34") (pin "2") (pinfunction "CATHODE_1_2") (pintype "passive"))
      (node (ref "U34") (pin "3") (pinfunction "CATHODE_2_3") (pintype "passive"))
      (node (ref "U35") (pin "2") (pinfunction "CATHODE_1_2") (pintype "passive"))
      (node (ref "U35") (pin "3") (pinfunction "CATHODE_2_3") (pintype "passive"))
      (node (ref "U37") (pin "2") (pinfunction "CATHODE_1_2") (pintype "passive"))
      (node (ref "U37") (pin "3") (pinfunction "CATHODE_2_3") (pintype "passive"))
      (node (ref "U38") (pin "2") (pinfunction "CATHODE_1_2") (pintype "passive"))
      (node (ref "U38") (pin "3") (pinfunction "CATHODE_2_3") (pintype "passive"))
      (node (ref "U43") (pin "2") (pinfunction "C_2") (pintype "passive"))
      (node (ref "U44") (pin "2") (pinfunction "C_2") (pintype "passive"))
      (node (ref "U5") (pin "3") (pinfunction "3_3") (pintype "passive"))
      (node (ref "U6") (pin "3") (pinfunction "3_3") (pintype "passive"))
    )
    (net (code "77") (name "unconnected-(U3-MO-Pad25)") (class "Default")
      (node (ref "U3") (pin "25") (pinfunction "MO_25") (pintype "passive+no_connect"))
    )
    (net (code "78") (name "unconnected-(U5-Pad1)") (class "Default")
      (node (ref "U5") (pin "1") (pinfunction "1_1") (pintype "passive"))
    )
    (net (code "79") (name "unconnected-(U5-Pad4)") (class "Default")
      (node (ref "U5") (pin "4") (pinfunction "4_4") (pintype "passive"))
    )
    (net (code "80") (name "unconnected-(U5-Pad7)") (class "Default")
      (node (ref "U5") (pin "7") (pinfunction "7_7") (pintype "passive"))
    )
    (net (code "81") (name "unconnected-(U6-Pad1)") (class "Default")
      (node (ref "U6") (pin "1") (pinfunction "1_1") (pintype "passive"))
    )
    (net (code "82") (name "unconnected-(U6-Pad4)") (class "Default")
      (node (ref "U6") (pin "4") (pinfunction "4_4") (pintype "passive"))
    )
    (net (code "83") (name "unconnected-(U6-Pad7)") (class "Default")
      (node (ref "U6") (pin "7") (pinfunction "7_7") (pintype "passive"))
    )
    (net (code "84") (name "unconnected-(U22-MS1-Pad2)") (class "Default")
      (node (ref "U22") (pin "2") (pinfunction "MS1_2") (pintype "passive"))
    )
    (net (code "85") (name "unconnected-(U22-MS2-Pad3)") (class "Default")
      (node (ref "U22") (pin "3") (pinfunction "MS2_3") (pintype "passive"))
    )
    (net (code "86") (name "unconnected-(U22-MS3-Pad4)") (class "Default")
      (node (ref "U22") (pin "4") (pinfunction "MS3_4") (pintype "passive"))
    )
    (net (code "87") (name "unconnected-(U23-MS1-Pad2)") (class "Default")
      (node (ref "U23") (pin "2") (pinfunction "MS1_2") (pintype "passive"))
    )
    (net (code "88") (name "unconnected-(U23-MS2-Pad3)") (class "Default")
      (node (ref "U23") (pin "3") (pinfunction "MS2_3") (pintype "passive"))
    )
    (net (code "89") (name "unconnected-(U23-MS3-Pad4)") (class "Default")
      (node (ref "U23") (pin "4") (pinfunction "MS3_4") (pintype "passive"))
    )
    (net (code "90") (name "unconnected-(U26-5A-Pad11)") (class "Default")
      (node (ref "U26") (pin "11") (pinfunction "5A_11") (pintype "passive+no_connect"))
    )
    (net (code "91") (name "unconnected-(U26-5Y-Pad10)") (class "Default")
      (node (ref "U26") (pin "10") (pinfunction "5Y_10") (pintype "passive+no_connect"))
    )
    (net (code "92") (name "unconnected-(U26-6A-Pad13)") (class "Default")
      (node (ref "U26") (pin "13") (pinfunction "6A_13") (pintype "passive+no_connect"))
    )
    (net (code "93") (name "unconnected-(U26-6Y-Pad12)") (class "Default")
      (node (ref "U26") (pin "12") (pinfunction "6Y_12") (pintype "passive+no_connect"))
    )
  )
)
